# Digital_Analog_Startup_Board.net
KiCad netlist of a schematic drawn in EAGLE
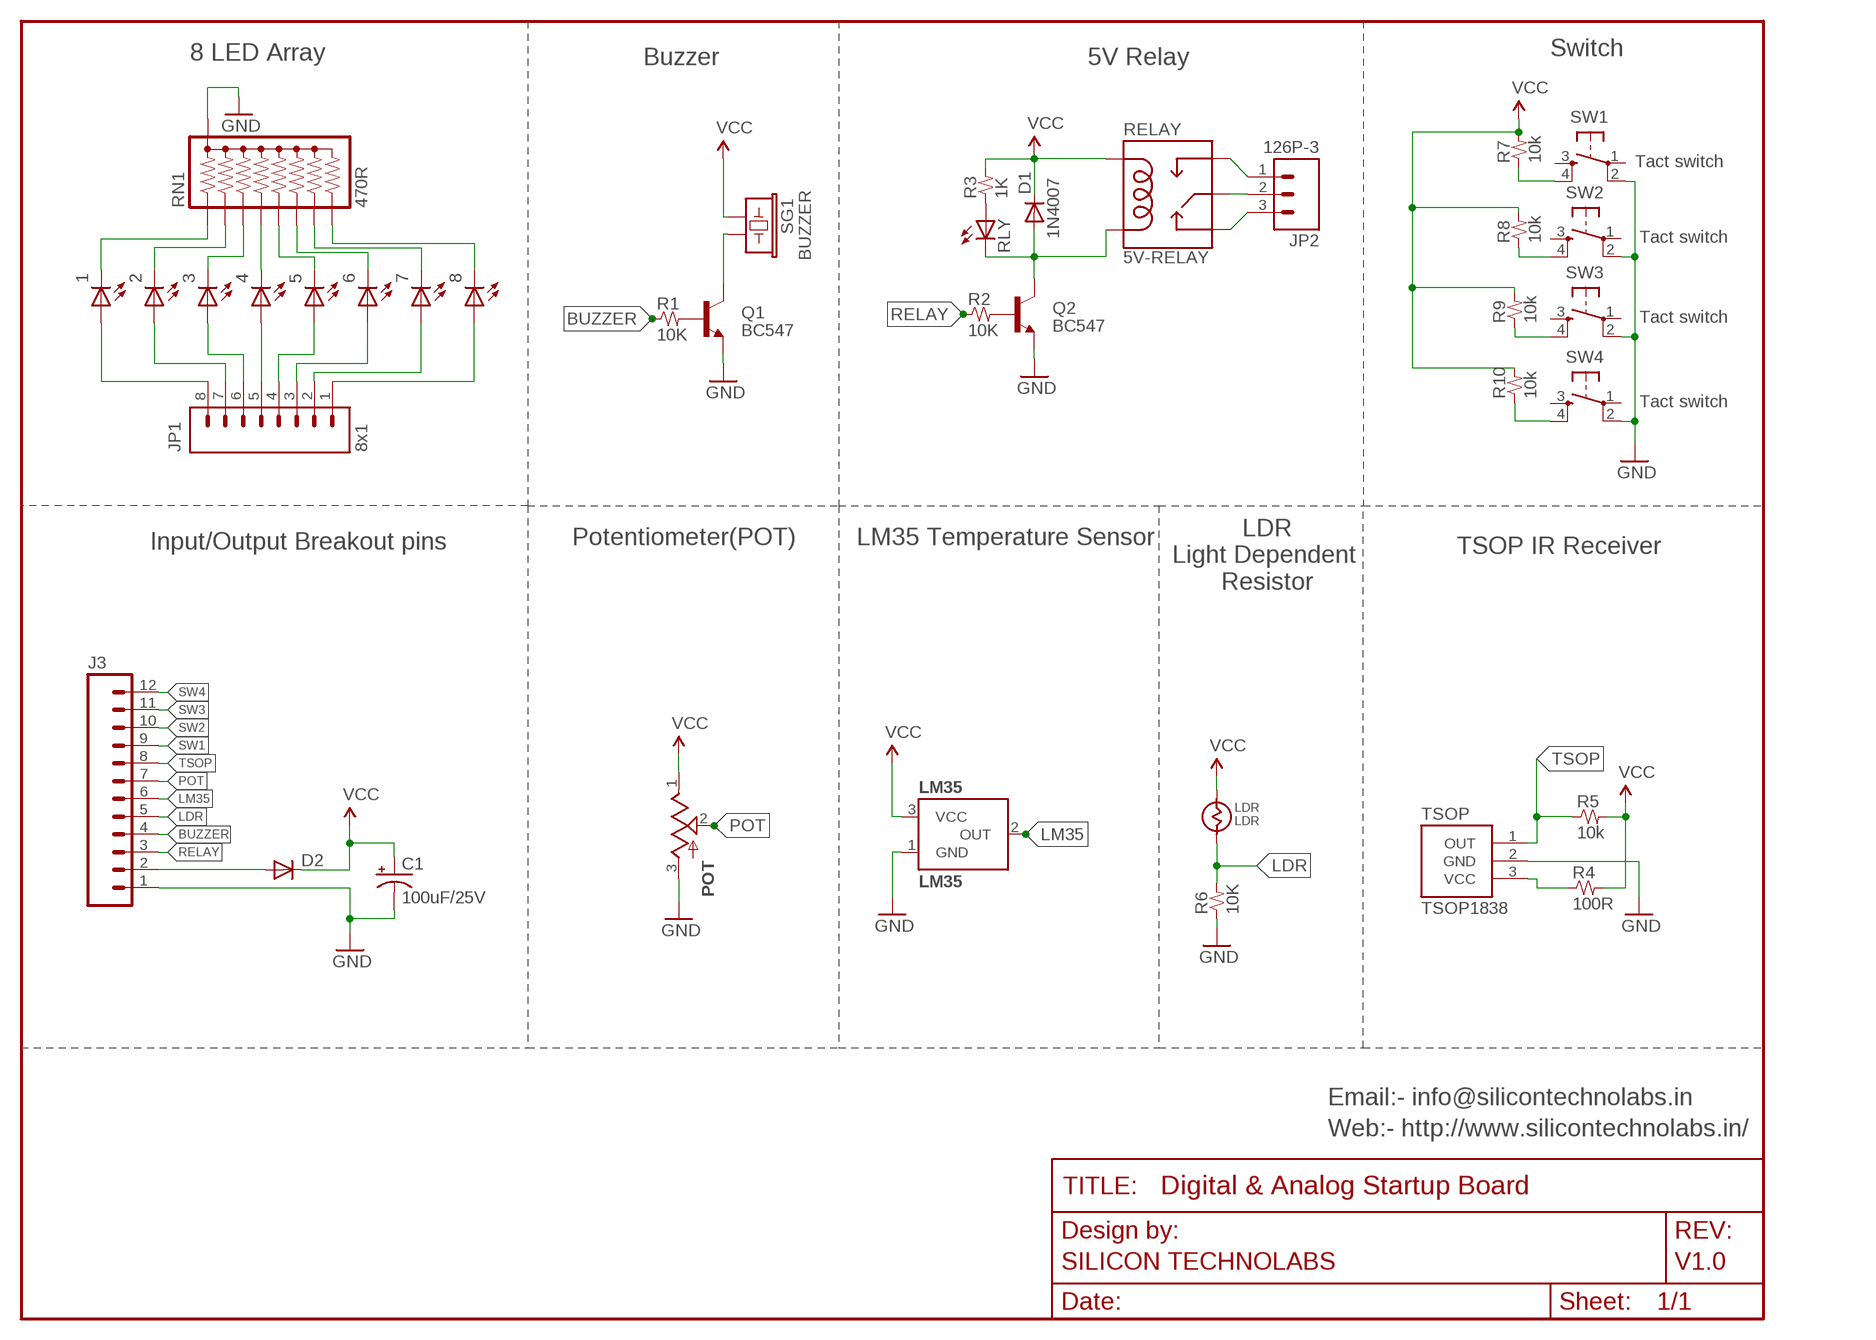
[diagram p0: schematic, sheet 1]

(export (version "E")
  (design (tool "Eeschema 10.0.6"))
  (components
    (comp (ref "1")
      (value "LED3MM")
      (footprint "eagle-import:3MM")
      (libsource (lib "eagle-import") (part "LED3MM"))
    )
    (comp (ref "2")
      (value "LED3MM")
      (footprint "eagle-import:3MM")
      (libsource (lib "eagle-import") (part "LED3MM"))
    )
    (comp (ref "3")
      (value "LED3MM")
      (footprint "eagle-import:3MM")
      (libsource (lib "eagle-import") (part "LED3MM"))
    )
    (comp (ref "4")
      (value "LED3MM")
      (footprint "eagle-import:3MM")
      (libsource (lib "eagle-import") (part "LED3MM"))
    )
    (comp (ref "5")
      (value "LED3MM")
      (footprint "eagle-import:3MM")
      (libsource (lib "eagle-import") (part "LED3MM"))
    )
    (comp (ref "5V-RELAY")
      (value "RELAY")
      (footprint "eagle-import:RELAY-LEONE")
      (libsource (lib "eagle-import") (part "RELAYPTH5"))
    )
    (comp (ref "6")
      (value "LED3MM")
      (footprint "eagle-import:3MM")
      (libsource (lib "eagle-import") (part "LED3MM"))
    )
    (comp (ref "7")
      (value "LED3MM")
      (footprint "eagle-import:3MM")
      (libsource (lib "eagle-import") (part "LED3MM"))
    )
    (comp (ref "8")
      (value "LED3MM")
      (footprint "eagle-import:3MM")
      (libsource (lib "eagle-import") (part "LED3MM"))
    )
    (comp (ref "C1")
      (value "100uF/25V")
      (footprint "eagle-import:CPOL-RADIAL-100UF-25V")
      (libsource (lib "eagle-import") (part "CPOL100/25"))
    )
    (comp (ref "D1")
      (value "1N4007")
      (footprint "eagle-import:DIODE-1N4007")
      (libsource (lib "eagle-import") (part "1N4007"))
    )
    (comp (ref "D2")
      (value "1N4007")
      (footprint "eagle-import:DIODE-1N4007")
      (libsource (lib "eagle-import") (part "1N4007"))
    )
    (comp (ref "J3")
      (value "M12MACHINE-PIN_LOCK")
      (footprint "eagle-import:1X12_MACHINE-PIN-HEADER_LOCK.004")
      (libsource (lib "eagle-import") (part "M12MACHINE-PIN_LOCK"))
    )
    (comp (ref "JP1")
      (value "8x1")
      (footprint "eagle-import:1X08_LOCK")
      (libsource (lib "eagle-import") (part "M08"))
    )
    (comp (ref "JP2")
      (value "126P-3")
      (footprint "eagle-import:1X03_SCREWTERM")
      (libsource (lib "eagle-import") (part "M03S"))
    )
    (comp (ref "LDR")
      (value "LDR")
      (footprint "eagle-import:LDR")
      (libsource (lib "eagle-import") (part "LDR"))
    )
    (comp (ref "LM35")
      (value "LM35")
      (footprint "eagle-import:TO-92")
      (libsource (lib "eagle-import") (part "LM35"))
    )
    (comp (ref "POT")
      (value "POTCH")
      (footprint "eagle-import:POT-CH")
      (libsource (lib "eagle-import") (part "POTCH"))
    )
    (comp (ref "Q1")
      (value "BC547")
      (footprint "eagle-import:TO-92")
      (libsource (lib "eagle-import") (part "BC547"))
    )
    (comp (ref "Q2")
      (value "BC547")
      (footprint "eagle-import:TO-92")
      (libsource (lib "eagle-import") (part "BC547"))
    )
    (comp (ref "R1")
      (value "10K")
      (footprint "eagle-import:AXIAL-0.4")
      (libsource (lib "eagle-import") (part "RESISTOR-PTH-1/4W"))
    )
    (comp (ref "R2")
      (value "10K")
      (footprint "eagle-import:AXIAL-0.4")
      (libsource (lib "eagle-import") (part "RESISTOR-PTH-1/4W"))
    )
    (comp (ref "R3")
      (value "1K")
      (footprint "eagle-import:AXIAL-0.4")
      (libsource (lib "eagle-import") (part "RESISTOR-PTH-1/4W"))
    )
    (comp (ref "R4")
      (value "100R")
      (footprint "eagle-import:AXIAL-0.4")
      (libsource (lib "eagle-import") (part "RESISTOR-PTH-1/4W"))
    )
    (comp (ref "R5")
      (value "10k")
      (footprint "eagle-import:AXIAL-0.4")
      (libsource (lib "eagle-import") (part "RESISTOR-PTH-1/4W"))
    )
    (comp (ref "R6")
      (value "10K")
      (footprint "eagle-import:AXIAL-0.4")
      (libsource (lib "eagle-import") (part "RESISTOR-PTH-1/4W"))
    )
    (comp (ref "R7")
      (value "10k")
      (footprint "eagle-import:AXIAL-0.4")
      (libsource (lib "eagle-import") (part "RESISTOR-PTH-1/4W"))
    )
    (comp (ref "R8")
      (value "10k")
      (footprint "eagle-import:AXIAL-0.4")
      (libsource (lib "eagle-import") (part "RESISTOR-PTH-1/4W"))
    )
    (comp (ref "R9")
      (value "10k")
      (footprint "eagle-import:AXIAL-0.4")
      (libsource (lib "eagle-import") (part "RESISTOR-PTH-1/4W"))
    )
    (comp (ref "R10")
      (value "10k")
      (footprint "eagle-import:AXIAL-0.4")
      (libsource (lib "eagle-import") (part "RESISTOR-PTH-1/4W"))
    )
    (comp (ref "RLY")
      (value "LED3MM")
      (footprint "eagle-import:3MM")
      (libsource (lib "eagle-import") (part "LED3MM"))
    )
    (comp (ref "RN1")
      (value "470R")
      (footprint "eagle-import:RPACK-SIP-PTH-8-LP")
      (libsource (lib "eagle-import") (part "RPACK8"))
    )
    (comp (ref "SG1")
      (value "BUZZER")
      (footprint "eagle-import:BUZZER-12MM")
      (libsource (lib "eagle-import") (part "BUZZERPTH"))
    )
    (comp (ref "SW1")
      (value "Tact switch")
      (footprint "eagle-import:TACTILE-PTH")
      (libsource (lib "eagle-import") (part "TACTILE-SWITCH-5MM"))
    )
    (comp (ref "SW2")
      (value "Tact switch")
      (footprint "eagle-import:TACTILE-PTH")
      (libsource (lib "eagle-import") (part "TACTILE-SWITCH-5MM"))
    )
    (comp (ref "SW3")
      (value "Tact switch")
      (footprint "eagle-import:TACTILE-PTH")
      (libsource (lib "eagle-import") (part "TACTILE-SWITCH-5MM"))
    )
    (comp (ref "SW4")
      (value "Tact switch")
      (footprint "eagle-import:TACTILE-PTH")
      (libsource (lib "eagle-import") (part "TACTILE-SWITCH-5MM"))
    )
    (comp (ref "TSOP")
      (value "TSOP1838")
      (footprint "eagle-import:BRM-2508")
      (libsource (lib "eagle-import") (part "BRM-2A18RA"))
    )
  )
  (nets
    (net (code "1") (name "BUZZER") (class "Default")
      (node (ref "J3") (pin "4") (pinfunction "4_4") (pintype "passive"))
      (node (ref "R1") (pin "P$1") (pinfunction "1_P$1") (pintype "passive"))
    )
    (net (code "2") (name "GND") (class "Default")
      (node (ref "C1") (pin "2") (pinfunction "-_2") (pintype "passive"))
      (node (ref "J3") (pin "1") (pinfunction "1_1") (pintype "passive"))
      (node (ref "LM35") (pin "1") (pinfunction "GND_1") (pintype "bidirectional"))
      (node (ref "POT") (pin "3") (pinfunction "3_3") (pintype "passive"))
      (node (ref "Q1") (pin "1") (pinfunction "E_1") (pintype "passive"))
      (node (ref "Q2") (pin "1") (pinfunction "E_1") (pintype "passive"))
      (node (ref "R6") (pin "P$1") (pinfunction "1_P$1") (pintype "passive"))
      (node (ref "RN1") (pin "P$1") (pinfunction "1_P$1") (pintype "passive"))
      (node (ref "SW1") (pin "2") (pinfunction "2_2") (pintype "passive"))
      (node (ref "SW2") (pin "2") (pinfunction "2_2") (pintype "passive"))
      (node (ref "SW3") (pin "2") (pinfunction "2_2") (pintype "passive"))
      (node (ref "SW4") (pin "2") (pinfunction "2_2") (pintype "passive"))
      (node (ref "TSOP") (pin "2") (pinfunction "GND_2") (pintype "bidirectional"))
    )
    (net (code "3") (name "LDR") (class "Default")
      (node (ref "J3") (pin "5") (pinfunction "5_5") (pintype "passive"))
      (node (ref "LDR") (pin "2") (pinfunction "2_2") (pintype "bidirectional"))
      (node (ref "R6") (pin "P$2") (pinfunction "2_P$2") (pintype "passive"))
    )
    (net (code "4") (name "LM35") (class "Default")
      (node (ref "J3") (pin "6") (pinfunction "6_6") (pintype "passive"))
      (node (ref "LM35") (pin "2") (pinfunction "OUT_2") (pintype "bidirectional"))
    )
    (net (code "5") (name "Net-(1-C)") (class "Default")
      (node (ref "1") (pin "K") (pinfunction "C_K") (pintype "passive"))
      (node (ref "RN1") (pin "P$2") (pinfunction "2_P$2") (pintype "passive"))
    )
    (net (code "6") (name "Net-(1-PadA)") (class "Default")
      (node (ref "1") (pin "A") (pinfunction "A_A") (pintype "passive"))
      (node (ref "JP1") (pin "8") (pinfunction "8_8") (pintype "passive"))
    )
    (net (code "7") (name "Net-(2-C)") (class "Default")
      (node (ref "2") (pin "K") (pinfunction "C_K") (pintype "passive"))
      (node (ref "RN1") (pin "P$3") (pinfunction "3_P$3") (pintype "passive"))
    )
    (net (code "8") (name "Net-(2-PadA)") (class "Default")
      (node (ref "2") (pin "A") (pinfunction "A_A") (pintype "passive"))
      (node (ref "JP1") (pin "7") (pinfunction "7_7") (pintype "passive"))
    )
    (net (code "9") (name "Net-(3-C)") (class "Default")
      (node (ref "3") (pin "K") (pinfunction "C_K") (pintype "passive"))
      (node (ref "RN1") (pin "P$4") (pinfunction "4_P$4") (pintype "passive"))
    )
    (net (code "10") (name "Net-(3-PadA)") (class "Default")
      (node (ref "3") (pin "A") (pinfunction "A_A") (pintype "passive"))
      (node (ref "JP1") (pin "6") (pinfunction "6_6") (pintype "passive"))
    )
    (net (code "11") (name "Net-(4-C)") (class "Default")
      (node (ref "4") (pin "K") (pinfunction "C_K") (pintype "passive"))
      (node (ref "RN1") (pin "P$5") (pinfunction "5_P$5") (pintype "passive"))
    )
    (net (code "12") (name "Net-(4-PadA)") (class "Default")
      (node (ref "4") (pin "A") (pinfunction "A_A") (pintype "passive"))
      (node (ref "JP1") (pin "5") (pinfunction "5_5") (pintype "passive"))
    )
    (net (code "13") (name "Net-(5-C)") (class "Default")
      (node (ref "5") (pin "K") (pinfunction "C_K") (pintype "passive"))
      (node (ref "RN1") (pin "P$6") (pinfunction "6_P$6") (pintype "passive"))
    )
    (net (code "14") (name "Net-(5-PadA)") (class "Default")
      (node (ref "5") (pin "A") (pinfunction "A_A") (pintype "passive"))
      (node (ref "JP1") (pin "4") (pinfunction "4_4") (pintype "passive"))
    )
    (net (code "15") (name "Net-(5V-RELAY-COIL1)") (class "Default")
      (node (ref "5V-RELAY") (pin "1") (pinfunction "COIL1_1") (pintype "bidirectional"))
      (node (ref "D1") (pin "A") (pinfunction "A_A") (pintype "passive"))
      (node (ref "Q2") (pin "3") (pinfunction "C_3") (pintype "passive"))
      (node (ref "RLY") (pin "K") (pinfunction "C_K") (pintype "passive"))
    )
    (net (code "16") (name "Net-(5V-RELAY-MAIN)") (class "Default")
      (node (ref "5V-RELAY") (pin "C") (pinfunction "MAIN_C") (pintype "bidirectional"))
      (node (ref "JP2") (pin "2") (pinfunction "2_2") (pintype "passive"))
    )
    (net (code "17") (name "Net-(5V-RELAY-PadNC)") (class "Default")
      (node (ref "5V-RELAY") (pin "NC") (pinfunction "NC_NC") (pintype "bidirectional"))
      (node (ref "JP2") (pin "3") (pinfunction "3_3") (pintype "passive"))
    )
    (net (code "18") (name "Net-(5V-RELAY-PadNO)") (class "Default")
      (node (ref "5V-RELAY") (pin "NO") (pinfunction "NO_NO") (pintype "bidirectional"))
      (node (ref "JP2") (pin "1") (pinfunction "1_1") (pintype "passive"))
    )
    (net (code "19") (name "Net-(6-C)") (class "Default")
      (node (ref "6") (pin "K") (pinfunction "C_K") (pintype "passive"))
      (node (ref "RN1") (pin "P$7") (pinfunction "7_P$7") (pintype "passive"))
    )
    (net (code "20") (name "Net-(6-PadA)") (class "Default")
      (node (ref "6") (pin "A") (pinfunction "A_A") (pintype "passive"))
      (node (ref "JP1") (pin "3") (pinfunction "3_3") (pintype "passive"))
    )
    (net (code "21") (name "Net-(7-C)") (class "Default")
      (node (ref "7") (pin "K") (pinfunction "C_K") (pintype "passive"))
      (node (ref "RN1") (pin "P$8") (pinfunction "8_P$8") (pintype "passive"))
    )
    (net (code "22") (name "Net-(7-PadA)") (class "Default")
      (node (ref "7") (pin "A") (pinfunction "A_A") (pintype "passive"))
      (node (ref "JP1") (pin "2") (pinfunction "2_2") (pintype "passive"))
    )
    (net (code "23") (name "Net-(8-C)") (class "Default")
      (node (ref "8") (pin "K") (pinfunction "C_K") (pintype "passive"))
      (node (ref "RN1") (pin "P$9") (pinfunction "9_P$9") (pintype "passive"))
    )
    (net (code "24") (name "Net-(8-PadA)") (class "Default")
      (node (ref "8") (pin "A") (pinfunction "A_A") (pintype "passive"))
      (node (ref "JP1") (pin "1") (pinfunction "1_1") (pintype "passive"))
    )
    (net (code "25") (name "Net-(D2-PadA)") (class "Default")
      (node (ref "D2") (pin "A") (pinfunction "A_A") (pintype "passive"))
      (node (ref "J3") (pin "2") (pinfunction "2_2") (pintype "passive"))
    )
    (net (code "26") (name "Net-(Q1-B)") (class "Default")
      (node (ref "Q1") (pin "2") (pinfunction "B_2") (pintype "passive"))
      (node (ref "R1") (pin "P$2") (pinfunction "2_P$2") (pintype "passive"))
    )
    (net (code "27") (name "Net-(Q1-C)") (class "Default")
      (node (ref "Q1") (pin "3") (pinfunction "C_3") (pintype "passive"))
      (node (ref "SG1") (pin "-") (pinfunction "2_-") (pintype "passive"))
    )
    (net (code "28") (name "Net-(Q2-B)") (class "Default")
      (node (ref "Q2") (pin "2") (pinfunction "B_2") (pintype "passive"))
      (node (ref "R2") (pin "P$2") (pinfunction "2_P$2") (pintype "passive"))
    )
    (net (code "29") (name "Net-(R3-1)") (class "Default")
      (node (ref "R3") (pin "P$1") (pinfunction "1_P$1") (pintype "passive"))
      (node (ref "RLY") (pin "A") (pinfunction "A_A") (pintype "passive"))
    )
    (net (code "30") (name "Net-(R4-1)") (class "Default")
      (node (ref "R4") (pin "P$1") (pinfunction "1_P$1") (pintype "passive"))
      (node (ref "TSOP") (pin "3") (pinfunction "VCC_3") (pintype "bidirectional"))
    )
    (net (code "31") (name "POT") (class "Default")
      (node (ref "J3") (pin "7") (pinfunction "7_7") (pintype "passive"))
      (node (ref "POT") (pin "2") (pinfunction "2_2") (pintype "passive"))
    )
    (net (code "32") (name "RELAY") (class "Default")
      (node (ref "J3") (pin "3") (pinfunction "3_3") (pintype "passive"))
      (node (ref "R2") (pin "P$1") (pinfunction "1_P$1") (pintype "passive"))
    )
    (net (code "33") (name "SW1") (class "Default")
      (node (ref "J3") (pin "9") (pinfunction "9_9") (pintype "passive"))
      (node (ref "R7") (pin "P$1") (pinfunction "1_P$1") (pintype "passive"))
      (node (ref "SW1") (pin "4") (pinfunction "4_4") (pintype "passive"))
    )
    (net (code "34") (name "SW2") (class "Default")
      (node (ref "J3") (pin "10") (pinfunction "10_10") (pintype "passive"))
      (node (ref "R8") (pin "P$1") (pinfunction "1_P$1") (pintype "passive"))
      (node (ref "SW2") (pin "4") (pinfunction "4_4") (pintype "passive"))
    )
    (net (code "35") (name "SW3") (class "Default")
      (node (ref "J3") (pin "11") (pinfunction "11_11") (pintype "passive"))
      (node (ref "R9") (pin "P$1") (pinfunction "1_P$1") (pintype "passive"))
      (node (ref "SW3") (pin "4") (pinfunction "4_4") (pintype "passive"))
    )
    (net (code "36") (name "SW4") (class "Default")
      (node (ref "J3") (pin "12") (pinfunction "12_12") (pintype "passive"))
      (node (ref "R10") (pin "P$1") (pinfunction "1_P$1") (pintype "passive"))
      (node (ref "SW4") (pin "4") (pinfunction "4_4") (pintype "passive"))
    )
    (net (code "37") (name "TSOP") (class "Default")
      (node (ref "J3") (pin "8") (pinfunction "8_8") (pintype "passive"))
      (node (ref "R5") (pin "P$1") (pinfunction "1_P$1") (pintype "passive"))
      (node (ref "TSOP") (pin "1") (pinfunction "OUT_1") (pintype "bidirectional"))
    )
    (net (code "38") (name "VCC") (class "Default")
      (node (ref "5V-RELAY") (pin "2") (pinfunction "COIL2_2") (pintype "bidirectional"))
      (node (ref "C1") (pin "1") (pinfunction "+_1") (pintype "passive"))
      (node (ref "D1") (pin "C") (pinfunction "C_C") (pintype "passive"))
      (node (ref "D2") (pin "C") (pinfunction "C_C") (pintype "passive"))
      (node (ref "LDR") (pin "1") (pinfunction "1_1") (pintype "bidirectional"))
      (node (ref "LM35") (pin "3") (pinfunction "VCC_3") (pintype "bidirectional"))
      (node (ref "POT") (pin "1") (pinfunction "1_1") (pintype "passive"))
      (node (ref "R10") (pin "P$2") (pinfunction "2_P$2") (pintype "passive"))
      (node (ref "R3") (pin "P$2") (pinfunction "2_P$2") (pintype "passive"))
      (node (ref "R4") (pin "P$2") (pinfunction "2_P$2") (pintype "passive"))
      (node (ref "R5") (pin "P$2") (pinfunction "2_P$2") (pintype "passive"))
      (node (ref "R7") (pin "P$2") (pinfunction "2_P$2") (pintype "passive"))
      (node (ref "R8") (pin "P$2") (pinfunction "2_P$2") (pintype "passive"))
      (node (ref "R9") (pin "P$2") (pinfunction "2_P$2") (pintype "passive"))
      (node (ref "SG1") (pin "+") (pinfunction "1_+") (pintype "passive"))
    )
    (net (code "39") (name "unconnected-(SW1-Pad1)") (class "Default")
      (node (ref "SW1") (pin "1") (pinfunction "1_1") (pintype "passive"))
    )
    (net (code "40") (name "unconnected-(SW1-Pad3)") (class "Default")
      (node (ref "SW1") (pin "3") (pinfunction "3_3") (pintype "passive"))
    )
    (net (code "41") (name "unconnected-(SW2-Pad1)") (class "Default")
      (node (ref "SW2") (pin "1") (pinfunction "1_1") (pintype "passive"))
    )
    (net (code "42") (name "unconnected-(SW2-Pad3)") (class "Default")
      (node (ref "SW2") (pin "3") (pinfunction "3_3") (pintype "passive"))
    )
    (net (code "43") (name "unconnected-(SW3-Pad1)") (class "Default")
      (node (ref "SW3") (pin "1") (pinfunction "1_1") (pintype "passive"))
    )
    (net (code "44") (name "unconnected-(SW3-Pad3)") (class "Default")
      (node (ref "SW3") (pin "3") (pinfunction "3_3") (pintype "passive"))
    )
    (net (code "45") (name "unconnected-(SW4-Pad1)") (class "Default")
      (node (ref "SW4") (pin "1") (pinfunction "1_1") (pintype "passive"))
    )
    (net (code "46") (name "unconnected-(SW4-Pad3)") (class "Default")
      (node (ref "SW4") (pin "3") (pinfunction "3_3") (pintype "passive"))
    )
  )
)
